# USB_To_Serial.net
KiCad netlist of a schematic drawn in Altium Designer
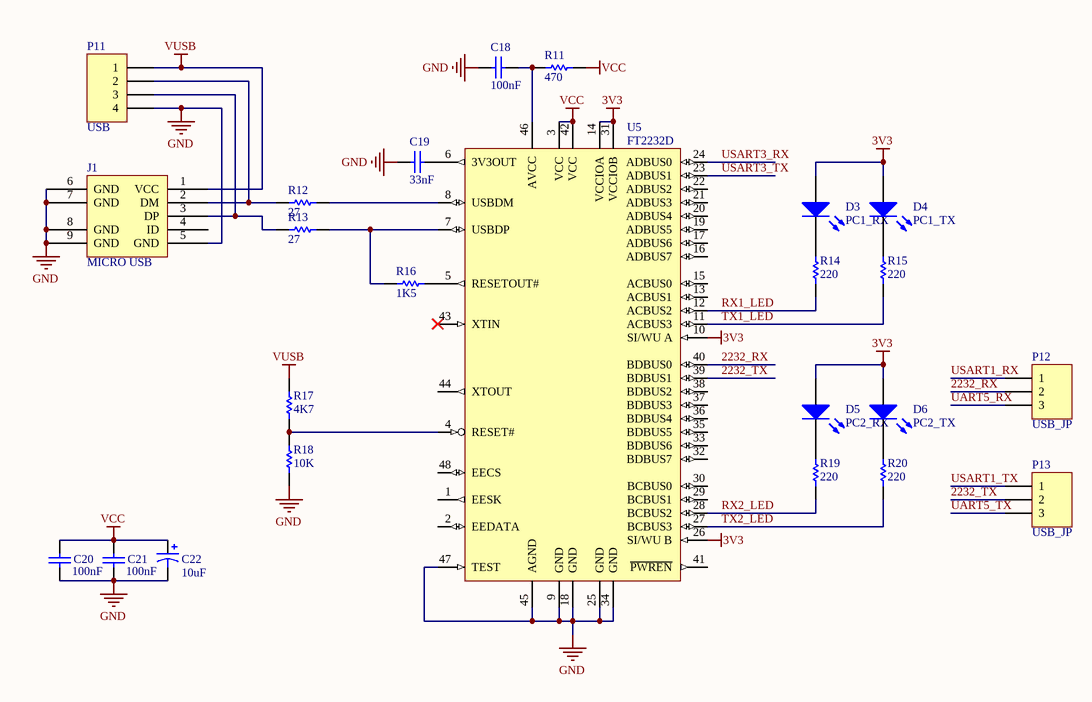
[diagram p0: USB To Serial.SchDoc]

(export (version "E")
  (design (tool "Eeschema 10.0.6"))
  (components
    (comp (ref "C18")
      (value "100nF")
      (footprint "0603-CAP")
      (description "Capacitor")
      (fields (field (name "PUBLISHER") "Altium Limited"))
      (libsource (lib "BarelangRobotics") (part "Cap"))
    )
    (comp (ref "C19")
      (value "33nF")
      (footprint "0603-CAP")
      (description "Capacitor")
      (fields (field (name "PUBLISHER") "Altium Limited"))
      (libsource (lib "BarelangRobotics") (part "Cap"))
    )
    (comp (ref "C20")
      (value "100nF")
      (footprint "0603-CAP")
      (description "Capacitor")
      (fields (field (name "PUBLISHER") "Altium Limited"))
      (libsource (lib "BarelangRobotics") (part "Cap"))
    )
    (comp (ref "C21")
      (value "100nF")
      (footprint "0603-CAP")
      (description "Capacitor")
      (fields (field (name "PUBLISHER") "Altium Limited"))
      (libsource (lib "BarelangRobotics") (part "Cap"))
    )
    (comp (ref "C22")
      (value "10uF")
      (footprint "SV-C")
      (description "Polarized Capacitor (Axial)")
      (fields (field (name "PUBLISHER") "Altium Limited"))
      (libsource (lib "BarelangRobotics") (part "Cap Pol"))
    )
    (comp (ref "D3")
      (value "PC1_RX")
      (footprint "CHIPLED_0603")
      (description "Typical INFRARED GaAs LED")
      (fields (field (name "PUBLISHER") "Altium Limited"))
      (libsource (lib "BarelangRobotics") (part "LED"))
    )
    (comp (ref "D4")
      (value "PC1_TX")
      (footprint "CHIPLED_0603")
      (description "Typical INFRARED GaAs LED")
      (fields (field (name "PUBLISHER") "Altium Limited"))
      (libsource (lib "BarelangRobotics") (part "LED"))
    )
    (comp (ref "D5")
      (value "PC2_RX")
      (footprint "CHIPLED_0603")
      (description "Typical INFRARED GaAs LED")
      (fields (field (name "PUBLISHER") "Altium Limited"))
      (libsource (lib "BarelangRobotics") (part "LED"))
    )
    (comp (ref "D6")
      (value "PC2_TX")
      (footprint "CHIPLED_0603")
      (description "Typical INFRARED GaAs LED")
      (fields (field (name "PUBLISHER") "Altium Limited"))
      (libsource (lib "BarelangRobotics") (part "LED"))
    )
    (comp (ref "J1")
      (value "MICRO USB")
      (footprint "USB_MICRO")
      (libsource (lib "BarelangRobotics") (part "MICRO USB"))
    )
    (comp (ref "P11")
      (value "USB")
      (footprint "HDR1X4")
      (description "Header, 4-Pin")
      (fields (field (name "PUBLISHER") "Altium Limited"))
      (libsource (lib "BarelangRobotics") (part "Header 4"))
    )
    (comp (ref "P12")
      (value "USB_JP")
      (footprint "HDR1X3")
      (description "Header, 3-Pin")
      (fields (field (name "PUBLISHER") "Altium Limited"))
      (libsource (lib "BarelangRobotics") (part "Header 3"))
    )
    (comp (ref "P13")
      (value "USB_JP")
      (footprint "HDR1X3")
      (description "Header, 3-Pin")
      (fields (field (name "PUBLISHER") "Altium Limited"))
      (libsource (lib "BarelangRobotics") (part "Header 3"))
    )
    (comp (ref "R11")
      (value "470")
      (footprint "0603-RES")
      (description "Resistor")
      (fields (field (name "PUBLISHER") "Altium Limited"))
      (libsource (lib "BarelangRobotics") (part "Res"))
    )
    (comp (ref "R12")
      (value "27")
      (footprint "0603-RES")
      (description "Resistor")
      (fields (field (name "PUBLISHER") "Altium Limited"))
      (libsource (lib "BarelangRobotics") (part "Res"))
    )
    (comp (ref "R13")
      (value "27")
      (footprint "0603-RES")
      (description "Resistor")
      (fields (field (name "PUBLISHER") "Altium Limited"))
      (libsource (lib "BarelangRobotics") (part "Res"))
    )
    (comp (ref "R14")
      (value "220")
      (footprint "0603-RES")
      (description "Resistor")
      (fields (field (name "PUBLISHER") "Altium Limited"))
      (libsource (lib "BarelangRobotics") (part "Res"))
    )
    (comp (ref "R15")
      (value "220")
      (footprint "0603-RES")
      (description "Resistor")
      (fields (field (name "PUBLISHER") "Altium Limited"))
      (libsource (lib "BarelangRobotics") (part "Res"))
    )
    (comp (ref "R16")
      (value "1K5")
      (footprint "0603-RES")
      (description "Resistor")
      (fields (field (name "PUBLISHER") "Altium Limited"))
      (libsource (lib "BarelangRobotics") (part "Res"))
    )
    (comp (ref "R17")
      (value "4K7")
      (footprint "0603-RES")
      (description "Resistor")
      (fields (field (name "PUBLISHER") "Altium Limited"))
      (libsource (lib "BarelangRobotics") (part "Res"))
    )
    (comp (ref "R18")
      (value "10K")
      (footprint "0603-RES")
      (description "Resistor")
      (fields (field (name "PUBLISHER") "Altium Limited"))
      (libsource (lib "BarelangRobotics") (part "Res"))
    )
    (comp (ref "R19")
      (value "220")
      (footprint "0603-RES")
      (description "Resistor")
      (fields (field (name "PUBLISHER") "Altium Limited"))
      (libsource (lib "BarelangRobotics") (part "Res"))
    )
    (comp (ref "R20")
      (value "220")
      (footprint "0603-RES")
      (description "Resistor")
      (fields (field (name "PUBLISHER") "Altium Limited"))
      (libsource (lib "BarelangRobotics") (part "Res"))
    )
    (comp (ref "U5")
      (value "FT2232D")
      (footprint "QFP-48N")
      (description "Dual USB UART/FIFO Chip, LQFP-48")
      (fields (field (name "PUBLISHER") "Altium Limited"))
      (libsource (lib "BarelangRobotics") (part "FT2232D"))
    )
  )
  (nets
    (net (code "1") (name "/2232_RX") (class "Default")
      (node (ref "P12") (pin "2") (pinfunction "2_2") (pintype "passive"))
      (node (ref "U5") (pin "40") (pinfunction "BDBUS0_40") (pintype "bidirectional"))
    )
    (net (code "2") (name "/2232_TX") (class "Default")
      (node (ref "P13") (pin "2") (pinfunction "2_2") (pintype "passive"))
      (node (ref "U5") (pin "39") (pinfunction "BDBUS1_39") (pintype "bidirectional"))
    )
    (net (code "3") (name "/RX1_LED") (class "Default")
      (node (ref "R14") (pin "1") (pinfunction "1_1") (pintype "passive"))
      (node (ref "U5") (pin "12") (pinfunction "ACBUS2_12") (pintype "bidirectional"))
    )
    (net (code "4") (name "/RX2_LED") (class "Default")
      (node (ref "R19") (pin "1") (pinfunction "1_1") (pintype "passive"))
      (node (ref "U5") (pin "28") (pinfunction "BCBUS2_28") (pintype "bidirectional"))
    )
    (net (code "5") (name "/TX1_LED") (class "Default")
      (node (ref "R15") (pin "1") (pinfunction "1_1") (pintype "passive"))
      (node (ref "U5") (pin "11") (pinfunction "ACBUS3_11") (pintype "bidirectional"))
    )
    (net (code "6") (name "/TX2_LED") (class "Default")
      (node (ref "R20") (pin "1") (pinfunction "1_1") (pintype "passive"))
      (node (ref "U5") (pin "27") (pinfunction "BCBUS3_27") (pintype "bidirectional"))
    )
    (net (code "7") (name "/UART5_RX") (class "Default")
      (node (ref "P12") (pin "3") (pinfunction "3_3") (pintype "passive"))
    )
    (net (code "8") (name "/UART5_TX") (class "Default")
      (node (ref "P13") (pin "3") (pinfunction "3_3") (pintype "passive"))
    )
    (net (code "9") (name "/USART1_RX") (class "Default")
      (node (ref "P12") (pin "1") (pinfunction "1_1") (pintype "passive"))
    )
    (net (code "10") (name "/USART1_TX") (class "Default")
      (node (ref "P13") (pin "1") (pinfunction "1_1") (pintype "passive"))
    )
    (net (code "11") (name "/USART3_RX") (class "Default")
      (node (ref "U5") (pin "24") (pinfunction "ADBUS0_24") (pintype "bidirectional"))
    )
    (net (code "12") (name "/USART3_TX") (class "Default")
      (node (ref "U5") (pin "23") (pinfunction "ADBUS1_23") (pintype "bidirectional"))
    )
    (net (code "13") (name "3V3") (class "Default")
      (node (ref "D3") (pin "1") (pinfunction "A_1") (pintype "passive"))
      (node (ref "D4") (pin "1") (pinfunction "A_1") (pintype "passive"))
      (node (ref "D5") (pin "1") (pinfunction "A_1") (pintype "passive"))
      (node (ref "D6") (pin "1") (pinfunction "A_1") (pintype "passive"))
      (node (ref "U5") (pin "10") (pinfunction "SI/WU_A_10") (pintype "input"))
      (node (ref "U5") (pin "14") (pinfunction "VCCIOA_14") (pintype "power_in"))
      (node (ref "U5") (pin "26") (pinfunction "SI/WU_B_26") (pintype "input"))
      (node (ref "U5") (pin "31") (pinfunction "VCCIOB_31") (pintype "power_in"))
    )
    (net (code "14") (name "GND") (class "Default")
      (node (ref "C18") (pin "1") (pinfunction "1_1") (pintype "passive"))
      (node (ref "C19") (pin "1") (pinfunction "1_1") (pintype "passive"))
      (node (ref "C20") (pin "1") (pinfunction "1_1") (pintype "passive"))
      (node (ref "C21") (pin "1") (pinfunction "1_1") (pintype "passive"))
      (node (ref "C22") (pin "2") (pinfunction "2_2") (pintype "passive"))
      (node (ref "J1") (pin "5") (pinfunction "GND_5") (pintype "passive"))
      (node (ref "J1") (pin "6") (pinfunction "GND_6") (pintype "passive"))
      (node (ref "J1") (pin "7") (pinfunction "GND_7") (pintype "passive"))
      (node (ref "J1") (pin "8") (pinfunction "GND_8") (pintype "passive"))
      (node (ref "J1") (pin "9") (pinfunction "GND_9") (pintype "passive"))
      (node (ref "P11") (pin "4") (pinfunction "4_4") (pintype "passive"))
      (node (ref "R18") (pin "1") (pinfunction "1_1") (pintype "passive"))
      (node (ref "U5") (pin "18") (pinfunction "GND_18") (pintype "power_in"))
      (node (ref "U5") (pin "25") (pinfunction "GND_25") (pintype "power_in"))
      (node (ref "U5") (pin "34") (pinfunction "GND_34") (pintype "power_in"))
      (node (ref "U5") (pin "45") (pinfunction "AGND_45") (pintype "power_in"))
      (node (ref "U5") (pin "47") (pinfunction "TEST_47") (pintype "input"))
      (node (ref "U5") (pin "9") (pinfunction "GND_9") (pintype "power_in"))
    )
    (net (code "15") (name "Net-(D3-K)") (class "Default")
      (node (ref "D3") (pin "2") (pinfunction "K_2") (pintype "passive"))
      (node (ref "R14") (pin "2") (pinfunction "2_2") (pintype "passive"))
    )
    (net (code "16") (name "Net-(D4-K)") (class "Default")
      (node (ref "D4") (pin "2") (pinfunction "K_2") (pintype "passive"))
      (node (ref "R15") (pin "2") (pinfunction "2_2") (pintype "passive"))
    )
    (net (code "17") (name "Net-(D5-K)") (class "Default")
      (node (ref "D5") (pin "2") (pinfunction "K_2") (pintype "passive"))
      (node (ref "R19") (pin "2") (pinfunction "2_2") (pintype "passive"))
    )
    (net (code "18") (name "Net-(D6-K)") (class "Default")
      (node (ref "D6") (pin "2") (pinfunction "K_2") (pintype "passive"))
      (node (ref "R20") (pin "2") (pinfunction "2_2") (pintype "passive"))
    )
    (net (code "19") (name "Net-(J1-DM)") (class "Default")
      (node (ref "J1") (pin "2") (pinfunction "DM_2") (pintype "passive"))
      (node (ref "P11") (pin "2") (pinfunction "2_2") (pintype "passive"))
      (node (ref "R12") (pin "1") (pinfunction "1_1") (pintype "passive"))
    )
    (net (code "20") (name "Net-(J1-DP)") (class "Default")
      (node (ref "J1") (pin "3") (pinfunction "DP_3") (pintype "passive"))
      (node (ref "P11") (pin "3") (pinfunction "3_3") (pintype "passive"))
      (node (ref "R13") (pin "1") (pinfunction "1_1") (pintype "passive"))
    )
    (net (code "21") (name "Net-(U5-3V3OUT)") (class "Default")
      (node (ref "C19") (pin "2") (pinfunction "2_2") (pintype "passive"))
      (node (ref "U5") (pin "6") (pinfunction "3V3OUT_6") (pintype "output"))
    )
    (net (code "22") (name "Net-(U5-AVCC)") (class "Default")
      (node (ref "C18") (pin "2") (pinfunction "2_2") (pintype "passive"))
      (node (ref "R11") (pin "1") (pinfunction "1_1") (pintype "passive"))
      (node (ref "U5") (pin "46") (pinfunction "AVCC_46") (pintype "power_in"))
    )
    (net (code "23") (name "Net-(U5-RESET#)") (class "Default")
      (node (ref "R17") (pin "1") (pinfunction "1_1") (pintype "passive"))
      (node (ref "R18") (pin "2") (pinfunction "2_2") (pintype "passive"))
      (node (ref "U5") (pin "4") (pinfunction "RESET#_4") (pintype "input"))
    )
    (net (code "24") (name "Net-(U5-RESETOUT#)") (class "Default")
      (node (ref "R16") (pin "2") (pinfunction "2_2") (pintype "passive"))
      (node (ref "U5") (pin "5") (pinfunction "RESETOUT#_5") (pintype "output"))
    )
    (net (code "25") (name "Net-(U5-USBDM)") (class "Default")
      (node (ref "R12") (pin "2") (pinfunction "2_2") (pintype "passive"))
      (node (ref "U5") (pin "8") (pinfunction "USBDM_8") (pintype "bidirectional"))
    )
    (net (code "26") (name "Net-(U5-USBDP)") (class "Default")
      (node (ref "R13") (pin "2") (pinfunction "2_2") (pintype "passive"))
      (node (ref "R16") (pin "1") (pinfunction "1_1") (pintype "passive"))
      (node (ref "U5") (pin "7") (pinfunction "USBDP_7") (pintype "bidirectional"))
    )
    (net (code "27") (name "VCC") (class "Default")
      (node (ref "C20") (pin "2") (pinfunction "2_2") (pintype "passive"))
      (node (ref "C21") (pin "2") (pinfunction "2_2") (pintype "passive"))
      (node (ref "C22") (pin "1") (pinfunction "1_1") (pintype "passive"))
      (node (ref "R11") (pin "2") (pinfunction "2_2") (pintype "passive"))
      (node (ref "U5") (pin "3") (pinfunction "VCC_3") (pintype "power_in"))
      (node (ref "U5") (pin "42") (pinfunction "VCC_42") (pintype "power_in"))
    )
    (net (code "28") (name "VUSB") (class "Default")
      (node (ref "J1") (pin "1") (pinfunction "VCC_1") (pintype "passive"))
      (node (ref "P11") (pin "1") (pinfunction "1_1") (pintype "passive"))
      (node (ref "R17") (pin "2") (pinfunction "2_2") (pintype "passive"))
    )
    (net (code "29") (name "unconnected-(J1-ID-Pad4)") (class "Default")
      (node (ref "J1") (pin "4") (pinfunction "ID_4") (pintype "passive"))
    )
    (net (code "30") (name "unconnected-(U5-ACBUS0-Pad15)") (class "Default")
      (node (ref "U5") (pin "15") (pinfunction "ACBUS0_15") (pintype "bidirectional"))
    )
    (net (code "31") (name "unconnected-(U5-ACBUS1-Pad13)") (class "Default")
      (node (ref "U5") (pin "13") (pinfunction "ACBUS1_13") (pintype "bidirectional"))
    )
    (net (code "32") (name "unconnected-(U5-ADBUS2-Pad22)") (class "Default")
      (node (ref "U5") (pin "22") (pinfunction "ADBUS2_22") (pintype "bidirectional"))
    )
    (net (code "33") (name "unconnected-(U5-ADBUS3-Pad21)") (class "Default")
      (node (ref "U5") (pin "21") (pinfunction "ADBUS3_21") (pintype "bidirectional"))
    )
    (net (code "34") (name "unconnected-(U5-ADBUS4-Pad20)") (class "Default")
      (node (ref "U5") (pin "20") (pinfunction "ADBUS4_20") (pintype "bidirectional"))
    )
    (net (code "35") (name "unconnected-(U5-ADBUS5-Pad19)") (class "Default")
      (node (ref "U5") (pin "19") (pinfunction "ADBUS5_19") (pintype "bidirectional"))
    )
    (net (code "36") (name "unconnected-(U5-ADBUS6-Pad17)") (class "Default")
      (node (ref "U5") (pin "17") (pinfunction "ADBUS6_17") (pintype "bidirectional"))
    )
    (net (code "37") (name "unconnected-(U5-ADBUS7-Pad16)") (class "Default")
      (node (ref "U5") (pin "16") (pinfunction "ADBUS7_16") (pintype "bidirectional"))
    )
    (net (code "38") (name "unconnected-(U5-BCBUS0-Pad30)") (class "Default")
      (node (ref "U5") (pin "30") (pinfunction "BCBUS0_30") (pintype "bidirectional"))
    )
    (net (code "39") (name "unconnected-(U5-BCBUS1-Pad29)") (class "Default")
      (node (ref "U5") (pin "29") (pinfunction "BCBUS1_29") (pintype "bidirectional"))
    )
    (net (code "40") (name "unconnected-(U5-BDBUS2-Pad38)") (class "Default")
      (node (ref "U5") (pin "38") (pinfunction "BDBUS2_38") (pintype "bidirectional"))
    )
    (net (code "41") (name "unconnected-(U5-BDBUS3-Pad37)") (class "Default")
      (node (ref "U5") (pin "37") (pinfunction "BDBUS3_37") (pintype "bidirectional"))
    )
    (net (code "42") (name "unconnected-(U5-BDBUS4-Pad36)") (class "Default")
      (node (ref "U5") (pin "36") (pinfunction "BDBUS4_36") (pintype "bidirectional"))
    )
    (net (code "43") (name "unconnected-(U5-BDBUS5-Pad35)") (class "Default")
      (node (ref "U5") (pin "35") (pinfunction "BDBUS5_35") (pintype "bidirectional"))
    )
    (net (code "44") (name "unconnected-(U5-BDBUS6-Pad33)") (class "Default")
      (node (ref "U5") (pin "33") (pinfunction "BDBUS6_33") (pintype "bidirectional"))
    )
    (net (code "45") (name "unconnected-(U5-BDBUS7-Pad32)") (class "Default")
      (node (ref "U5") (pin "32") (pinfunction "BDBUS7_32") (pintype "bidirectional"))
    )
    (net (code "46") (name "unconnected-(U5-EECS-Pad48)") (class "Default")
      (node (ref "U5") (pin "48") (pinfunction "EECS_48") (pintype "bidirectional"))
    )
    (net (code "47") (name "unconnected-(U5-EEDATA-Pad2)") (class "Default")
      (node (ref "U5") (pin "2") (pinfunction "EEDATA_2") (pintype "bidirectional"))
    )
    (net (code "48") (name "unconnected-(U5-EESK-Pad1)") (class "Default")
      (node (ref "U5") (pin "1") (pinfunction "EESK_1") (pintype "output"))
    )
    (net (code "49") (name "unconnected-(U5-XTIN-Pad43)") (class "Default")
      (node (ref "U5") (pin "43") (pinfunction "XTIN_43") (pintype "input+no_connect"))
    )
    (net (code "50") (name "unconnected-(U5-XTOUT-Pad44)") (class "Default")
      (node (ref "U5") (pin "44") (pinfunction "XTOUT_44") (pintype "output"))
    )
    (net (code "51") (name "unconnected-(U5-~{PWREN}-Pad41)") (class "Default")
      (node (ref "U5") (pin "41") (pinfunction "~{PWREN}_41") (pintype "output"))
    )
  )
)
